# expansionBreakout.net
KiCad netlist of a schematic drawn in Altium Designer
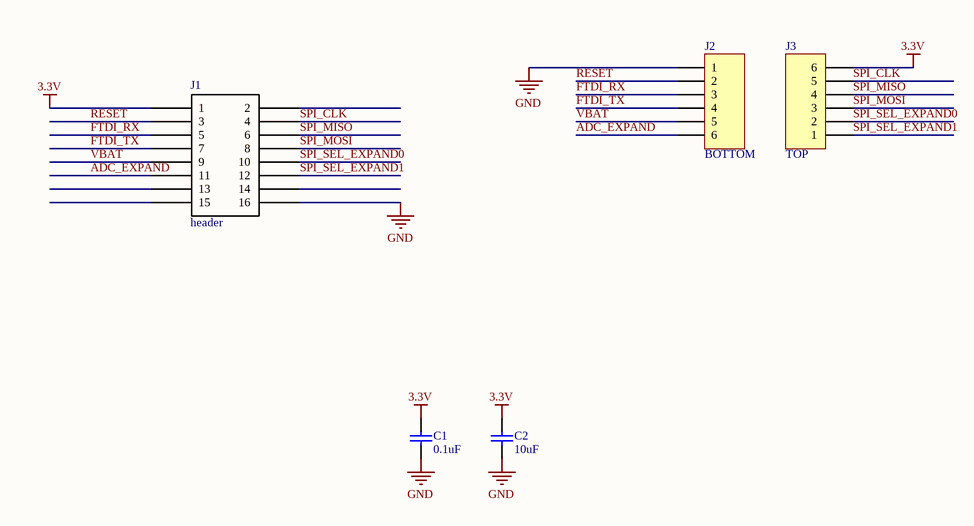
[diagram p0: expansionBreakout.SchDoc]

(export (version "E")
  (design (tool "Eeschema 10.0.6"))
  (components
    (comp (ref "C1")
      (value "0.1uF")
      (footprint "CAPC1005L")
      (description "Capacitor")
      (fields (field (name "PUBLISHER") "Altium Limited"))
      (libsource (lib "Miscellaneous Devices") (part "Cap"))
    )
    (comp (ref "C2")
      (value "10uF")
      (footprint "CAPC1608L")
      (description "Capacitor (Semiconductor SIM Model)")
      (fields (field (name "Comment") "Cap Semi") (field (name "PUBLISHER") "Altium Limited"))
      (libsource (lib "Miscellaneous Devices") (part "Cap Semi"))
    )
    (comp (ref "J1")
      (value "header")
      (footprint "HEADERSM 8X2")
      (libsource (lib "mrone") (part "HEADER 8X2"))
    )
    (comp (ref "J2")
      (value "BOTTOM")
      (footprint "HDR1X6")
      (description "Header, 6-Pin")
      (fields (field (name "PUBLISHER") "Altium Limited"))
      (libsource (lib "") (part "Header 6_1"))
    )
    (comp (ref "J3")
      (value "TOP")
      (footprint "HDR1X6")
      (description "Header, 6-Pin")
      (fields (field (name "PUBLISHER") "Altium Limited"))
      (libsource (lib "Miscellaneous Connectors") (part "Header 6"))
    )
  )
  (nets
    (net (code "1") (name "/ADC_EXPAND") (class "Default")
      (node (ref "J1") (pin "11") (pinfunction "11_11") (pintype "passive"))
      (node (ref "J2") (pin "6") (pinfunction "6_6") (pintype "passive"))
    )
    (net (code "2") (name "/FTDI_RX") (class "Default")
      (node (ref "J1") (pin "5") (pinfunction "5_5") (pintype "passive"))
      (node (ref "J2") (pin "3") (pinfunction "3_3") (pintype "passive"))
    )
    (net (code "3") (name "/FTDI_TX") (class "Default")
      (node (ref "J1") (pin "7") (pinfunction "7_7") (pintype "passive"))
      (node (ref "J2") (pin "4") (pinfunction "4_4") (pintype "passive"))
    )
    (net (code "4") (name "/RESET") (class "Default")
      (node (ref "J1") (pin "3") (pinfunction "3_3") (pintype "passive"))
      (node (ref "J2") (pin "2") (pinfunction "2_2") (pintype "passive"))
    )
    (net (code "5") (name "/SPI_CLK") (class "Default")
      (node (ref "J1") (pin "4") (pinfunction "4_4") (pintype "passive"))
      (node (ref "J3") (pin "5") (pinfunction "5_5") (pintype "passive"))
    )
    (net (code "6") (name "/SPI_MISO") (class "Default")
      (node (ref "J1") (pin "6") (pinfunction "6_6") (pintype "passive"))
      (node (ref "J3") (pin "4") (pinfunction "4_4") (pintype "passive"))
    )
    (net (code "7") (name "/SPI_MOSI") (class "Default")
      (node (ref "J1") (pin "8") (pinfunction "8_8") (pintype "passive"))
      (node (ref "J3") (pin "3") (pinfunction "3_3") (pintype "passive"))
    )
    (net (code "8") (name "/SPI_SEL_EXPAND0") (class "Default")
      (node (ref "J1") (pin "10") (pinfunction "10_10") (pintype "passive"))
      (node (ref "J3") (pin "2") (pinfunction "2_2") (pintype "passive"))
    )
    (net (code "9") (name "/SPI_SEL_EXPAND1") (class "Default")
      (node (ref "J1") (pin "12") (pinfunction "12_12") (pintype "passive"))
      (node (ref "J3") (pin "1") (pinfunction "1_1") (pintype "passive"))
    )
    (net (code "10") (name "/VBAT") (class "Default")
      (node (ref "J1") (pin "9") (pinfunction "9_9") (pintype "passive"))
      (node (ref "J2") (pin "5") (pinfunction "5_5") (pintype "passive"))
    )
    (net (code "11") (name "3.3V") (class "Default")
      (node (ref "C1") (pin "2") (pinfunction "2_2") (pintype "passive"))
      (node (ref "C2") (pin "2") (pinfunction "2_2") (pintype "passive"))
      (node (ref "J1") (pin "1") (pinfunction "1_1") (pintype "passive"))
      (node (ref "J3") (pin "6") (pinfunction "6_6") (pintype "passive"))
    )
    (net (code "12") (name "GND") (class "Default")
      (node (ref "C1") (pin "1") (pinfunction "1_1") (pintype "passive"))
      (node (ref "C2") (pin "1") (pinfunction "1_1") (pintype "passive"))
      (node (ref "J1") (pin "16") (pinfunction "16_16") (pintype "passive"))
      (node (ref "J2") (pin "1") (pinfunction "1_1") (pintype "passive"))
    )
    (net (code "13") (name "unconnected-(J1-Pad2)") (class "Default")
      (node (ref "J1") (pin "2") (pinfunction "2_2") (pintype "passive"))
    )
    (net (code "14") (name "unconnected-(J1-Pad13)") (class "Default")
      (node (ref "J1") (pin "13") (pinfunction "13_13") (pintype "passive"))
    )
    (net (code "15") (name "unconnected-(J1-Pad14)") (class "Default")
      (node (ref "J1") (pin "14") (pinfunction "14_14") (pintype "passive"))
    )
    (net (code "16") (name "unconnected-(J1-Pad15)") (class "Default")
      (node (ref "J1") (pin "15") (pinfunction "15_15") (pintype "passive"))
    )
  )
)
